# M2_Shield_Proto_V1_3.net
KiCad netlist of a schematic drawn in EAGLE
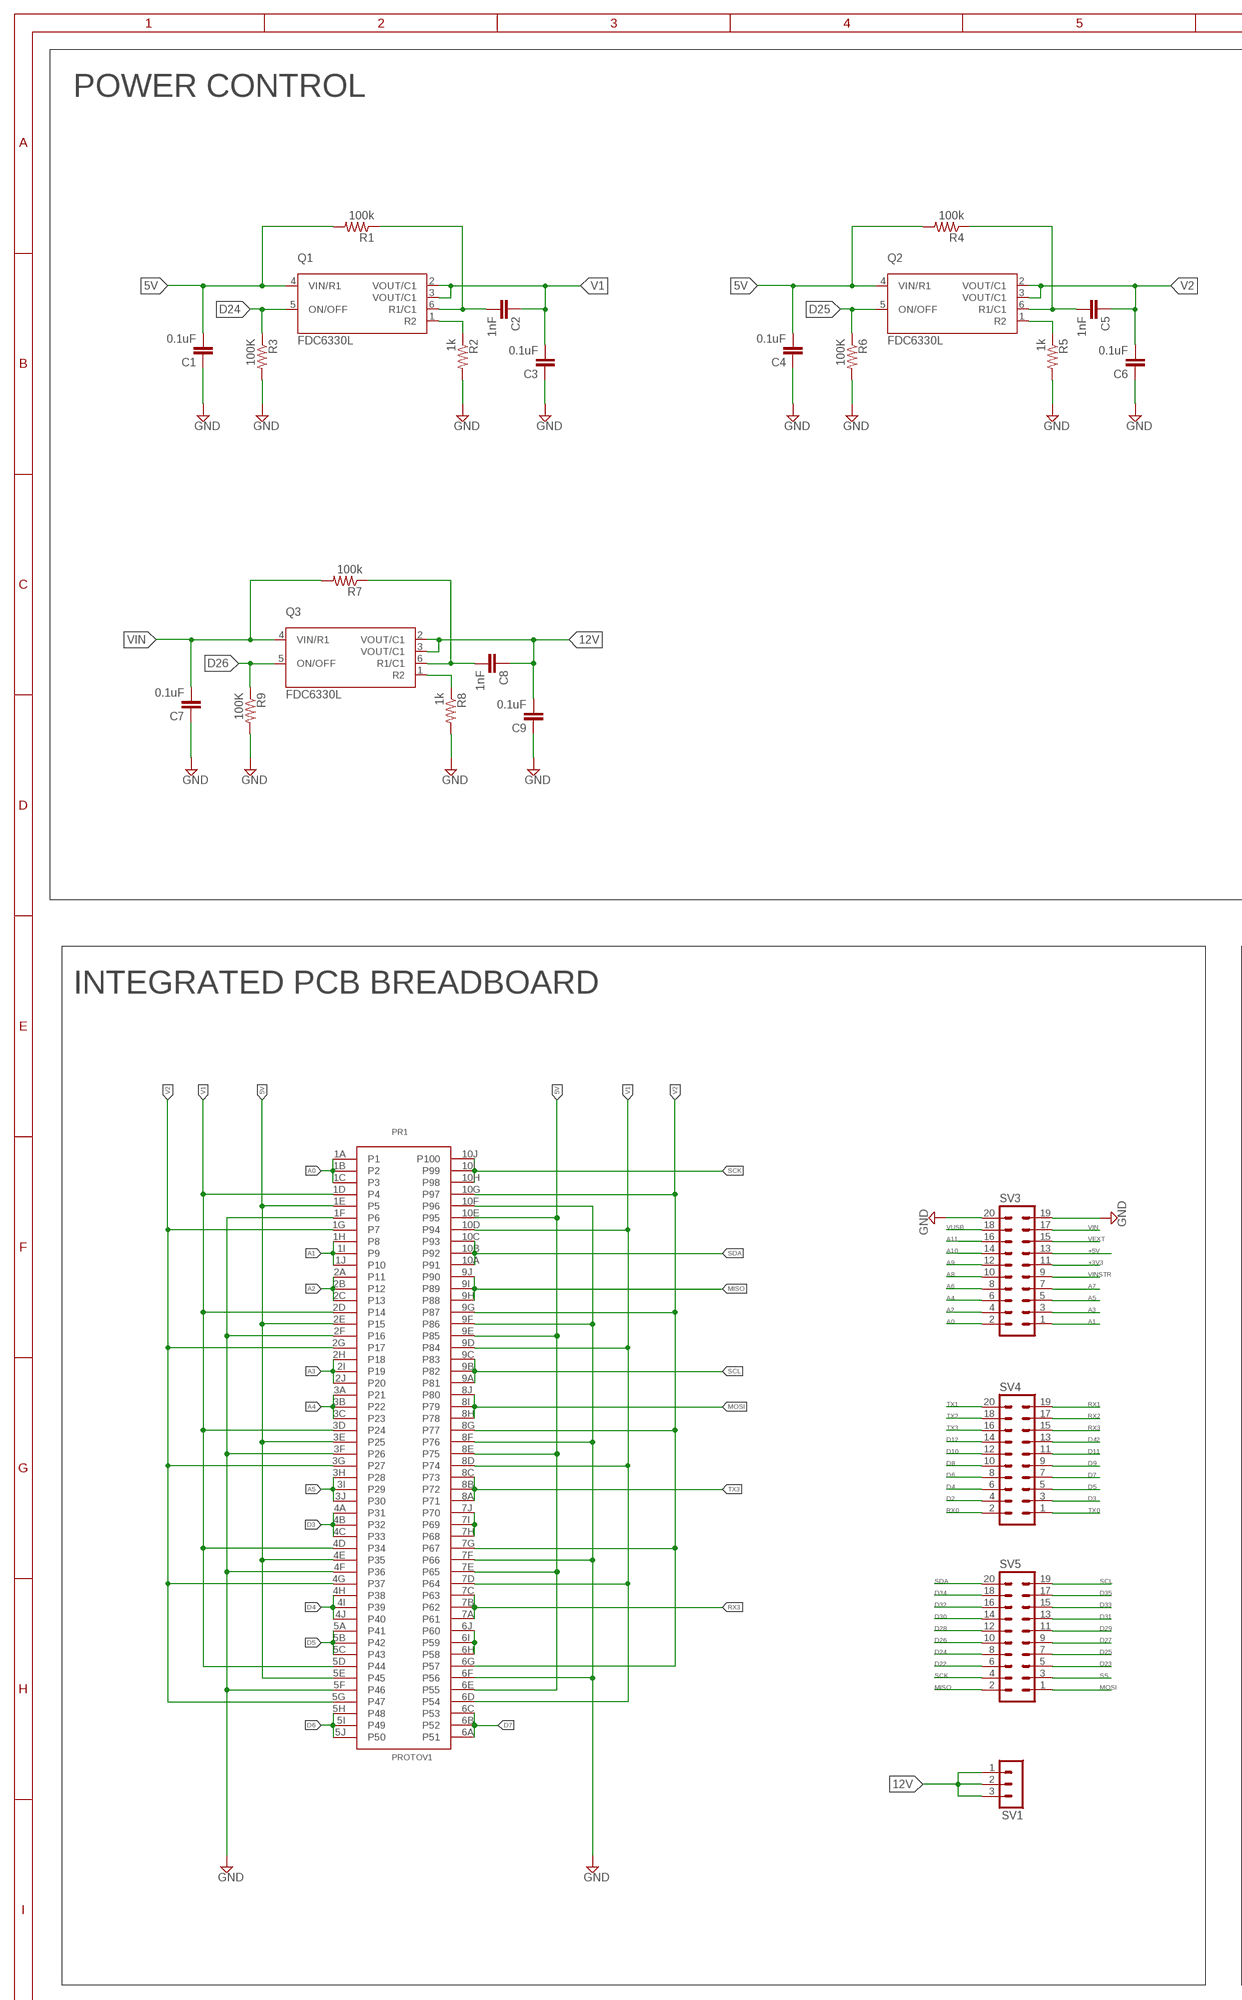
[diagram p0: schematic, sheet 1, part 1 of 2]
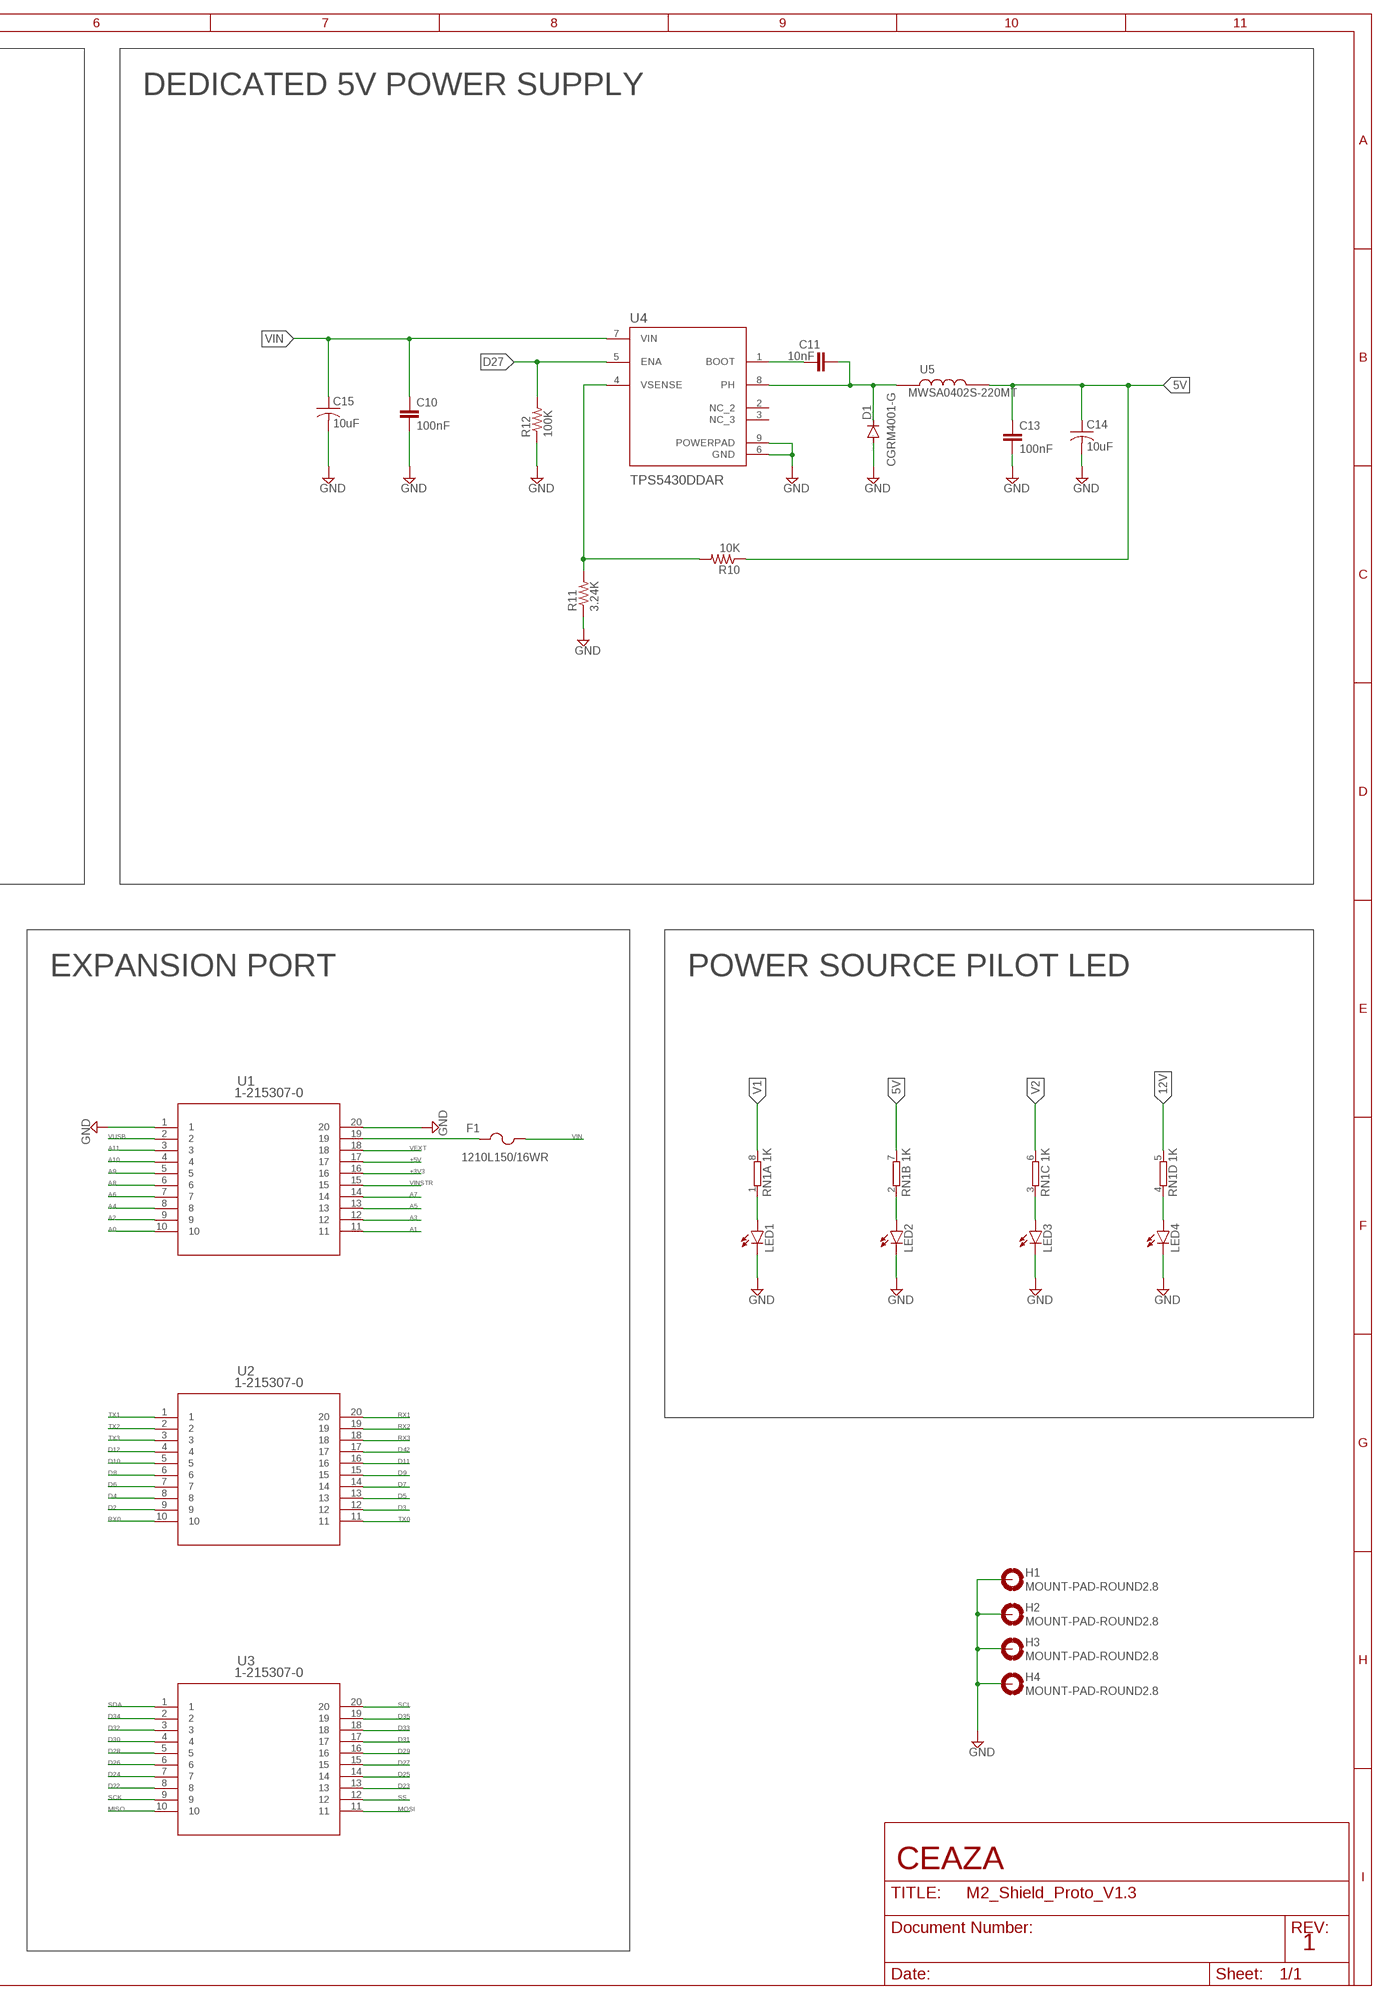
[diagram p1: schematic, sheet 1, part 2 of 2]

(export (version "E")
  (design (tool "Eeschema 10.0.6"))
  (components
    (comp (ref "C1")
      (value "0.1uF")
      (footprint "eagle-import:C0603")
      (libsource (lib "eagle-import") (part "C-EUC0603"))
    )
    (comp (ref "C2")
      (value "1nF")
      (footprint "eagle-import:C0603")
      (libsource (lib "eagle-import") (part "C-EUC0603"))
    )
    (comp (ref "C3")
      (value "0.1uF")
      (footprint "eagle-import:C0603")
      (libsource (lib "eagle-import") (part "C-EUC0603"))
    )
    (comp (ref "C4")
      (value "0.1uF")
      (footprint "eagle-import:C0603")
      (libsource (lib "eagle-import") (part "C-EUC0603"))
    )
    (comp (ref "C5")
      (value "1nF")
      (footprint "eagle-import:C0603")
      (libsource (lib "eagle-import") (part "C-EUC0603"))
    )
    (comp (ref "C6")
      (value "0.1uF")
      (footprint "eagle-import:C0603")
      (libsource (lib "eagle-import") (part "C-EUC0603"))
    )
    (comp (ref "C7")
      (value "0.1uF")
      (footprint "eagle-import:C0603")
      (libsource (lib "eagle-import") (part "C-EUC0603"))
    )
    (comp (ref "C8")
      (value "1nF")
      (footprint "eagle-import:C0603")
      (libsource (lib "eagle-import") (part "C-EUC0603"))
    )
    (comp (ref "C9")
      (value "0.1uF")
      (footprint "eagle-import:C0603")
      (libsource (lib "eagle-import") (part "C-EUC0603"))
    )
    (comp (ref "C10")
      (value "100nF")
      (footprint "eagle-import:C0603")
      (libsource (lib "eagle-import") (part "C-EUC0603"))
    )
    (comp (ref "C11")
      (value "10nF")
      (footprint "eagle-import:C0603")
      (libsource (lib "eagle-import") (part "C-EUC0603"))
    )
    (comp (ref "C13")
      (value "100nF")
      (footprint "eagle-import:C0603")
      (libsource (lib "eagle-import") (part "C-EUC0603"))
    )
    (comp (ref "C14")
      (value "10uF")
      (footprint "eagle-import:C0603")
      (libsource (lib "eagle-import") (part "C-USC0603"))
    )
    (comp (ref "C15")
      (value "10uF")
      (footprint "eagle-import:C0603")
      (libsource (lib "eagle-import") (part "C-USC0603"))
    )
    (comp (ref "D1")
      (value "CGRM4001-G")
      (footprint "eagle-import:SOD-123_MINI-SMA")
      (libsource (lib "eagle-import") (part "CGRM400-G1"))
    )
    (comp (ref "F1")
      (value "1210L150/16WR")
      (footprint "eagle-import:1210LSERIES")
      (libsource (lib "eagle-import") (part "1210L150/16WR"))
    )
    (comp (ref "H1")
      (value "MOUNT-PAD-ROUND2.8")
      (footprint "eagle-import:2,8-PAD")
      (libsource (lib "eagle-import") (part "MOUNT-PAD-ROUND2.8"))
    )
    (comp (ref "H2")
      (value "MOUNT-PAD-ROUND2.8")
      (footprint "eagle-import:2,8-PAD")
      (libsource (lib "eagle-import") (part "MOUNT-PAD-ROUND2.8"))
    )
    (comp (ref "H3")
      (value "MOUNT-PAD-ROUND2.8")
      (footprint "eagle-import:2,8-PAD")
      (libsource (lib "eagle-import") (part "MOUNT-PAD-ROUND2.8"))
    )
    (comp (ref "H4")
      (value "MOUNT-PAD-ROUND2.8")
      (footprint "eagle-import:2,8-PAD")
      (libsource (lib "eagle-import") (part "MOUNT-PAD-ROUND2.8"))
    )
    (comp (ref "LED1")
      (value "LEDCHIP-LED0805")
      (footprint "eagle-import:CHIP-LED0805")
      (libsource (lib "eagle-import") (part "LEDCHIP-LED0805"))
    )
    (comp (ref "LED2")
      (value "LEDCHIP-LED0805")
      (footprint "eagle-import:CHIP-LED0805")
      (libsource (lib "eagle-import") (part "LEDCHIP-LED0805"))
    )
    (comp (ref "LED3")
      (value "LEDCHIP-LED0805")
      (footprint "eagle-import:CHIP-LED0805")
      (libsource (lib "eagle-import") (part "LEDCHIP-LED0805"))
    )
    (comp (ref "LED4")
      (value "LEDCHIP-LED0805")
      (footprint "eagle-import:CHIP-LED0805")
      (libsource (lib "eagle-import") (part "LEDCHIP-LED0805"))
    )
    (comp (ref "PR1")
      (value "PROTOV1")
      (footprint "eagle-import:PROTOV1")
      (libsource (lib "eagle-import") (part "PROTOV1"))
    )
    (comp (ref "Q1")
      (value "FDC6330L")
      (footprint "eagle-import:SOT95P280X110-6N")
      (fields (field (name "DIGI-KEY_PART_NUMBER") "FDC6330LCT-ND") (field (name "MF") "ON Semiconductor"))
      (libsource (lib "eagle-import") (part "FDC6330L"))
    )
    (comp (ref "Q2")
      (value "FDC6330L")
      (footprint "eagle-import:SOT95P280X110-6N")
      (fields (field (name "DIGI-KEY_PART_NUMBER") "FDC6330LCT-ND") (field (name "MF") "ON Semiconductor"))
      (libsource (lib "eagle-import") (part "FDC6330L"))
    )
    (comp (ref "Q3")
      (value "FDC6330L")
      (footprint "eagle-import:SOT95P280X110-6N")
      (fields (field (name "DIGI-KEY_PART_NUMBER") "FDC6330LCT-ND") (field (name "MF") "ON Semiconductor"))
      (libsource (lib "eagle-import") (part "FDC6330L"))
    )
    (comp (ref "R1")
      (value "100k")
      (footprint "eagle-import:R0603")
      (libsource (lib "eagle-import") (part "R-US_R0603"))
    )
    (comp (ref "R2")
      (value "1k")
      (footprint "eagle-import:R0603")
      (libsource (lib "eagle-import") (part "R-US_R0603"))
    )
    (comp (ref "R3")
      (value "100K")
      (footprint "eagle-import:R0603")
      (libsource (lib "eagle-import") (part "R-US_R0603"))
    )
    (comp (ref "R4")
      (value "100k")
      (footprint "eagle-import:R0603")
      (libsource (lib "eagle-import") (part "R-US_R0603"))
    )
    (comp (ref "R5")
      (value "1k")
      (footprint "eagle-import:R0603")
      (libsource (lib "eagle-import") (part "R-US_R0603"))
    )
    (comp (ref "R6")
      (value "100K")
      (footprint "eagle-import:R0603")
      (libsource (lib "eagle-import") (part "R-US_R0603"))
    )
    (comp (ref "R7")
      (value "100k")
      (footprint "eagle-import:R0603")
      (libsource (lib "eagle-import") (part "R-US_R0603"))
    )
    (comp (ref "R8")
      (value "1k")
      (footprint "eagle-import:R0603")
      (libsource (lib "eagle-import") (part "R-US_R0603"))
    )
    (comp (ref "R9")
      (value "100K")
      (footprint "eagle-import:R0603")
      (libsource (lib "eagle-import") (part "R-US_R0603"))
    )
    (comp (ref "R10")
      (value "10K")
      (footprint "eagle-import:R0603")
      (libsource (lib "eagle-import") (part "R-US_R0603"))
    )
    (comp (ref "R11")
      (value "3.24K")
      (footprint "eagle-import:R0603")
      (libsource (lib "eagle-import") (part "R-US_R0603"))
    )
    (comp (ref "R12")
      (value "100K")
      (footprint "eagle-import:R0603")
      (libsource (lib "eagle-import") (part "R-US_R0603"))
    )
    (comp (ref "RN1")
      (value "1K")
      (footprint "eagle-import:0603-ARV")
      (libsource (lib "eagle-import") (part "4R-N0603-ARV"))
    )
    (comp (ref "SV1")
      (value "MA03-1")
      (footprint "eagle-import:MA03-1")
      (libsource (lib "eagle-import") (part "MA03-1"))
    )
    (comp (ref "SV3")
      (value "MA10-2")
      (footprint "eagle-import:MA10-2")
      (libsource (lib "eagle-import") (part "MA10-2"))
    )
    (comp (ref "SV4")
      (value "MA10-2")
      (footprint "eagle-import:MA10-2")
      (libsource (lib "eagle-import") (part "MA10-2"))
    )
    (comp (ref "SV5")
      (value "MA10-2")
      (footprint "eagle-import:MA10-2")
      (libsource (lib "eagle-import") (part "MA10-2"))
    )
    (comp (ref "U1")
      (value "1-215307-0")
      (footprint "eagle-import:1-215307-0")
      (libsource (lib "eagle-import") (part "1-215307-0"))
    )
    (comp (ref "U2")
      (value "1-215307-0")
      (footprint "eagle-import:1-215307-0")
      (libsource (lib "eagle-import") (part "1-215307-0"))
    )
    (comp (ref "U3")
      (value "1-215307-0")
      (footprint "eagle-import:1-215307-0")
      (libsource (lib "eagle-import") (part "1-215307-0"))
    )
    (comp (ref "U4")
      (value "TPS5430DDAR")
      (footprint "eagle-import:CONV_TPS5430DDAR")
      (fields (field (name "MF") "Texas Instruments"))
      (libsource (lib "eagle-import") (part "TPS5430DDAR"))
    )
    (comp (ref "U5")
      (value "MWSA0402S-220MT")
      (footprint "eagle-import:MWSA0402S-220MT")
      (libsource (lib "eagle-import") (part "MWSA0402S-220MT"))
    )
  )
  (nets
    (net (code "1") (name "/+3V3") (class "Default")
      (node (ref "SV3") (pin "11") (pinfunction "11_11") (pintype "passive"))
      (node (ref "U1") (pin "16") (pinfunction "16_16") (pintype "passive"))
    )
    (net (code "2") (name "/+5V") (class "Default")
      (node (ref "SV3") (pin "13") (pinfunction "13_13") (pintype "passive"))
      (node (ref "U1") (pin "17") (pinfunction "17_17") (pintype "passive"))
    )
    (net (code "3") (name "/A6") (class "Default")
      (node (ref "SV3") (pin "8") (pinfunction "8_8") (pintype "passive"))
      (node (ref "U1") (pin "7") (pinfunction "7_7") (pintype "passive"))
    )
    (net (code "4") (name "/A7") (class "Default")
      (node (ref "SV3") (pin "7") (pinfunction "7_7") (pintype "passive"))
      (node (ref "U1") (pin "14") (pinfunction "14_14") (pintype "passive"))
    )
    (net (code "5") (name "/A8") (class "Default")
      (node (ref "SV3") (pin "10") (pinfunction "10_10") (pintype "passive"))
      (node (ref "U1") (pin "6") (pinfunction "6_6") (pintype "passive"))
    )
    (net (code "6") (name "/A9") (class "Default")
      (node (ref "SV3") (pin "12") (pinfunction "12_12") (pintype "passive"))
      (node (ref "U1") (pin "5") (pinfunction "5_5") (pintype "passive"))
    )
    (net (code "7") (name "/A10") (class "Default")
      (node (ref "SV3") (pin "14") (pinfunction "14_14") (pintype "passive"))
      (node (ref "U1") (pin "4") (pinfunction "4_4") (pintype "passive"))
    )
    (net (code "8") (name "/A11") (class "Default")
      (node (ref "SV3") (pin "16") (pinfunction "16_16") (pintype "passive"))
      (node (ref "U1") (pin "3") (pinfunction "3_3") (pintype "passive"))
    )
    (net (code "9") (name "/D2") (class "Default")
      (node (ref "SV4") (pin "4") (pinfunction "4_4") (pintype "passive"))
      (node (ref "U2") (pin "9") (pinfunction "9_9") (pintype "passive"))
    )
    (net (code "10") (name "/D8") (class "Default")
      (node (ref "SV4") (pin "10") (pinfunction "10_10") (pintype "passive"))
      (node (ref "U2") (pin "6") (pinfunction "6_6") (pintype "passive"))
    )
    (net (code "11") (name "/D9") (class "Default")
      (node (ref "SV4") (pin "9") (pinfunction "9_9") (pintype "passive"))
      (node (ref "U2") (pin "15") (pinfunction "15_15") (pintype "passive"))
    )
    (net (code "12") (name "/D10") (class "Default")
      (node (ref "SV4") (pin "12") (pinfunction "12_12") (pintype "passive"))
      (node (ref "U2") (pin "5") (pinfunction "5_5") (pintype "passive"))
    )
    (net (code "13") (name "/D11") (class "Default")
      (node (ref "SV4") (pin "11") (pinfunction "11_11") (pintype "passive"))
      (node (ref "U2") (pin "16") (pinfunction "16_16") (pintype "passive"))
    )
    (net (code "14") (name "/D12") (class "Default")
      (node (ref "SV4") (pin "14") (pinfunction "14_14") (pintype "passive"))
      (node (ref "U2") (pin "4") (pinfunction "4_4") (pintype "passive"))
    )
    (net (code "15") (name "/D22") (class "Default")
      (node (ref "SV5") (pin "6") (pinfunction "6_6") (pintype "passive"))
      (node (ref "U3") (pin "8") (pinfunction "8_8") (pintype "passive"))
    )
    (net (code "16") (name "/D23") (class "Default")
      (node (ref "SV5") (pin "5") (pinfunction "5_5") (pintype "passive"))
      (node (ref "U3") (pin "13") (pinfunction "13_13") (pintype "passive"))
    )
    (net (code "17") (name "/D28") (class "Default")
      (node (ref "SV5") (pin "12") (pinfunction "12_12") (pintype "passive"))
      (node (ref "U3") (pin "5") (pinfunction "5_5") (pintype "passive"))
    )
    (net (code "18") (name "/D29") (class "Default")
      (node (ref "SV5") (pin "11") (pinfunction "11_11") (pintype "passive"))
      (node (ref "U3") (pin "16") (pinfunction "16_16") (pintype "passive"))
    )
    (net (code "19") (name "/D30") (class "Default")
      (node (ref "SV5") (pin "14") (pinfunction "14_14") (pintype "passive"))
      (node (ref "U3") (pin "4") (pinfunction "4_4") (pintype "passive"))
    )
    (net (code "20") (name "/D31") (class "Default")
      (node (ref "SV5") (pin "13") (pinfunction "13_13") (pintype "passive"))
      (node (ref "U3") (pin "17") (pinfunction "17_17") (pintype "passive"))
    )
    (net (code "21") (name "/D32") (class "Default")
      (node (ref "SV5") (pin "16") (pinfunction "16_16") (pintype "passive"))
      (node (ref "U3") (pin "3") (pinfunction "3_3") (pintype "passive"))
    )
    (net (code "22") (name "/D33") (class "Default")
      (node (ref "SV5") (pin "15") (pinfunction "15_15") (pintype "passive"))
      (node (ref "U3") (pin "18") (pinfunction "18_18") (pintype "passive"))
    )
    (net (code "23") (name "/D34") (class "Default")
      (node (ref "SV5") (pin "18") (pinfunction "18_18") (pintype "passive"))
      (node (ref "U3") (pin "2") (pinfunction "2_2") (pintype "passive"))
    )
    (net (code "24") (name "/D35") (class "Default")
      (node (ref "SV5") (pin "17") (pinfunction "17_17") (pintype "passive"))
      (node (ref "U3") (pin "19") (pinfunction "19_19") (pintype "passive"))
    )
    (net (code "25") (name "/D42") (class "Default")
      (node (ref "SV4") (pin "13") (pinfunction "13_13") (pintype "passive"))
      (node (ref "U2") (pin "17") (pinfunction "17_17") (pintype "passive"))
    )
    (net (code "26") (name "/RX0") (class "Default")
      (node (ref "SV4") (pin "2") (pinfunction "2_2") (pintype "passive"))
      (node (ref "U2") (pin "10") (pinfunction "10_10") (pintype "passive"))
    )
    (net (code "27") (name "/RX1") (class "Default")
      (node (ref "SV4") (pin "19") (pinfunction "19_19") (pintype "passive"))
      (node (ref "U2") (pin "20") (pinfunction "20_20") (pintype "passive"))
    )
    (net (code "28") (name "/RX2") (class "Default")
      (node (ref "SV4") (pin "17") (pinfunction "17_17") (pintype "passive"))
      (node (ref "U2") (pin "19") (pinfunction "19_19") (pintype "passive"))
    )
    (net (code "29") (name "/SS") (class "Default")
      (node (ref "SV5") (pin "3") (pinfunction "3_3") (pintype "passive"))
      (node (ref "U3") (pin "12") (pinfunction "12_12") (pintype "passive"))
    )
    (net (code "30") (name "/TX0") (class "Default")
      (node (ref "SV4") (pin "1") (pinfunction "1_1") (pintype "passive"))
      (node (ref "U2") (pin "11") (pinfunction "11_11") (pintype "passive"))
    )
    (net (code "31") (name "/TX1") (class "Default")
      (node (ref "SV4") (pin "20") (pinfunction "20_20") (pintype "passive"))
      (node (ref "U2") (pin "1") (pinfunction "1_1") (pintype "passive"))
    )
    (net (code "32") (name "/TX2") (class "Default")
      (node (ref "SV4") (pin "18") (pinfunction "18_18") (pintype "passive"))
      (node (ref "U2") (pin "2") (pinfunction "2_2") (pintype "passive"))
    )
    (net (code "33") (name "/VEXT") (class "Default")
      (node (ref "SV3") (pin "15") (pinfunction "15_15") (pintype "passive"))
      (node (ref "U1") (pin "18") (pinfunction "18_18") (pintype "passive"))
    )
    (net (code "34") (name "/VINSTR") (class "Default")
      (node (ref "SV3") (pin "9") (pinfunction "9_9") (pintype "passive"))
      (node (ref "U1") (pin "15") (pinfunction "15_15") (pintype "passive"))
    )
    (net (code "35") (name "/VUSB") (class "Default")
      (node (ref "SV3") (pin "18") (pinfunction "18_18") (pintype "passive"))
      (node (ref "U1") (pin "2") (pinfunction "2_2") (pintype "passive"))
    )
    (net (code "36") (name "5V") (class "Default")
      (node (ref "C1") (pin "2") (pinfunction "2_2") (pintype "passive"))
      (node (ref "C13") (pin "1") (pinfunction "1_1") (pintype "passive"))
      (node (ref "C14") (pin "1") (pinfunction "1_1") (pintype "passive"))
      (node (ref "C4") (pin "2") (pinfunction "2_2") (pintype "passive"))
      (node (ref "PR1") (pin "10E") (pinfunction "P95_10E") (pintype "bidirectional"))
      (node (ref "PR1") (pin "1E") (pinfunction "P5_1E") (pintype "bidirectional"))
      (node (ref "PR1") (pin "2E") (pinfunction "P15_2E") (pintype "bidirectional"))
      (node (ref "PR1") (pin "3E") (pinfunction "P25_3E") (pintype "bidirectional"))
      (node (ref "PR1") (pin "4E") (pinfunction "P35_4E") (pintype "bidirectional"))
      (node (ref "PR1") (pin "5E") (pinfunction "P45_5E") (pintype "bidirectional"))
      (node (ref "PR1") (pin "6E") (pinfunction "P55_6E") (pintype "bidirectional"))
      (node (ref "PR1") (pin "7E") (pinfunction "P65_7E") (pintype "bidirectional"))
      (node (ref "PR1") (pin "8E") (pinfunction "P75_8E") (pintype "bidirectional"))
      (node (ref "PR1") (pin "9E") (pinfunction "P85_9E") (pintype "bidirectional"))
      (node (ref "Q1") (pin "4") (pinfunction "VIN/R1_4") (pintype "input"))
      (node (ref "Q2") (pin "4") (pinfunction "VIN/R1_4") (pintype "input"))
      (node (ref "R1") (pin "2") (pinfunction "2_2") (pintype "passive"))
      (node (ref "R10") (pin "1") (pinfunction "1_1") (pintype "passive"))
      (node (ref "R4") (pin "2") (pinfunction "2_2") (pintype "passive"))
      (node (ref "RN1") (pin "7") (pinfunction "2_7") (pintype "passive"))
      (node (ref "U5") (pin "P$2") (pinfunction "P$2_P$2") (pintype "bidirectional"))
    )
    (net (code "37") (name "12V") (class "Default")
      (node (ref "C8") (pin "1") (pinfunction "1_1") (pintype "passive"))
      (node (ref "C9") (pin "2") (pinfunction "2_2") (pintype "passive"))
      (node (ref "Q3") (pin "2") (pinfunction "VOUT/C1_2") (pintype "output"))
      (node (ref "Q3") (pin "3") (pinfunction "VOUT/C1_3") (pintype "output"))
      (node (ref "RN1") (pin "5") (pinfunction "2_5") (pintype "passive"))
      (node (ref "SV1") (pin "1") (pinfunction "1_1") (pintype "passive"))
      (node (ref "SV1") (pin "2") (pinfunction "2_2") (pintype "passive"))
      (node (ref "SV1") (pin "3") (pinfunction "3_3") (pintype "passive"))
    )
    (net (code "38") (name "A0") (class "Default")
      (node (ref "PR1") (pin "1A") (pinfunction "P1_1A") (pintype "bidirectional"))
      (node (ref "PR1") (pin "1B") (pinfunction "P2_1B") (pintype "bidirectional"))
      (node (ref "PR1") (pin "1C") (pinfunction "P3_1C") (pintype "bidirectional"))
      (node (ref "SV3") (pin "2") (pinfunction "2_2") (pintype "passive"))
      (node (ref "U1") (pin "10") (pinfunction "10_10") (pintype "passive"))
    )
    (net (code "39") (name "A1") (class "Default")
      (node (ref "PR1") (pin "1H") (pinfunction "P8_1H") (pintype "bidirectional"))
      (node (ref "PR1") (pin "1I") (pinfunction "P9_1I") (pintype "bidirectional"))
      (node (ref "PR1") (pin "1J") (pinfunction "P10_1J") (pintype "bidirectional"))
      (node (ref "SV3") (pin "1") (pinfunction "1_1") (pintype "passive"))
      (node (ref "U1") (pin "11") (pinfunction "11_11") (pintype "passive"))
    )
    (net (code "40") (name "A2") (class "Default")
      (node (ref "PR1") (pin "2A") (pinfunction "P11_2A") (pintype "bidirectional"))
      (node (ref "PR1") (pin "2B") (pinfunction "P12_2B") (pintype "bidirectional"))
      (node (ref "PR1") (pin "2C") (pinfunction "P13_2C") (pintype "bidirectional"))
      (node (ref "SV3") (pin "4") (pinfunction "4_4") (pintype "passive"))
      (node (ref "U1") (pin "9") (pinfunction "9_9") (pintype "passive"))
    )
    (net (code "41") (name "A3") (class "Default")
      (node (ref "PR1") (pin "2H") (pinfunction "P18_2H") (pintype "bidirectional"))
      (node (ref "PR1") (pin "2I") (pinfunction "P19_2I") (pintype "bidirectional"))
      (node (ref "PR1") (pin "2J") (pinfunction "P20_2J") (pintype "bidirectional"))
      (node (ref "SV3") (pin "3") (pinfunction "3_3") (pintype "passive"))
      (node (ref "U1") (pin "12") (pinfunction "12_12") (pintype "passive"))
    )
    (net (code "42") (name "A4") (class "Default")
      (node (ref "PR1") (pin "3A") (pinfunction "P21_3A") (pintype "bidirectional"))
      (node (ref "PR1") (pin "3B") (pinfunction "P22_3B") (pintype "bidirectional"))
      (node (ref "PR1") (pin "3C") (pinfunction "P23_3C") (pintype "bidirectional"))
      (node (ref "SV3") (pin "6") (pinfunction "6_6") (pintype "passive"))
      (node (ref "U1") (pin "8") (pinfunction "8_8") (pintype "passive"))
    )
    (net (code "43") (name "A5") (class "Default")
      (node (ref "PR1") (pin "3H") (pinfunction "P28_3H") (pintype "bidirectional"))
      (node (ref "PR1") (pin "3I") (pinfunction "P29_3I") (pintype "bidirectional"))
      (node (ref "PR1") (pin "3J") (pinfunction "P30_3J") (pintype "bidirectional"))
      (node (ref "SV3") (pin "5") (pinfunction "5_5") (pintype "passive"))
      (node (ref "U1") (pin "13") (pinfunction "13_13") (pintype "passive"))
    )
    (net (code "44") (name "D3") (class "Default")
      (node (ref "PR1") (pin "4A") (pinfunction "P31_4A") (pintype "bidirectional"))
      (node (ref "PR1") (pin "4B") (pinfunction "P32_4B") (pintype "bidirectional"))
      (node (ref "PR1") (pin "4C") (pinfunction "P33_4C") (pintype "bidirectional"))
      (node (ref "SV4") (pin "3") (pinfunction "3_3") (pintype "passive"))
      (node (ref "U2") (pin "12") (pinfunction "12_12") (pintype "passive"))
    )
    (net (code "45") (name "D4") (class "Default")
      (node (ref "PR1") (pin "4H") (pinfunction "P38_4H") (pintype "bidirectional"))
      (node (ref "PR1") (pin "4I") (pinfunction "P39_4I") (pintype "bidirectional"))
      (node (ref "PR1") (pin "4J") (pinfunction "P40_4J") (pintype "bidirectional"))
      (node (ref "SV4") (pin "6") (pinfunction "6_6") (pintype "passive"))
      (node (ref "U2") (pin "8") (pinfunction "8_8") (pintype "passive"))
    )
    (net (code "46") (name "D5") (class "Default")
      (node (ref "PR1") (pin "5A") (pinfunction "P41_5A") (pintype "bidirectional"))
      (node (ref "PR1") (pin "5B") (pinfunction "P42_5B") (pintype "bidirectional"))
      (node (ref "PR1") (pin "5C") (pinfunction "P43_5C") (pintype "bidirectional"))
      (node (ref "SV4") (pin "5") (pinfunction "5_5") (pintype "passive"))
      (node (ref "U2") (pin "13") (pinfunction "13_13") (pintype "passive"))
    )
    (net (code "47") (name "D6") (class "Default")
      (node (ref "PR1") (pin "5H") (pinfunction "P48_5H") (pintype "bidirectional"))
      (node (ref "PR1") (pin "5I") (pinfunction "P49_5I") (pintype "bidirectional"))
      (node (ref "PR1") (pin "5J") (pinfunction "P50_5J") (pintype "bidirectional"))
      (node (ref "SV4") (pin "8") (pinfunction "8_8") (pintype "passive"))
      (node (ref "U2") (pin "7") (pinfunction "7_7") (pintype "passive"))
    )
    (net (code "48") (name "D7") (class "Default")
      (node (ref "PR1") (pin "6A") (pinfunction "P51_6A") (pintype "bidirectional"))
      (node (ref "PR1") (pin "6B") (pinfunction "P52_6B") (pintype "bidirectional"))
      (node (ref "PR1") (pin "6C") (pinfunction "P53_6C") (pintype "bidirectional"))
      (node (ref "SV4") (pin "7") (pinfunction "7_7") (pintype "passive"))
      (node (ref "U2") (pin "14") (pinfunction "14_14") (pintype "passive"))
    )
    (net (code "49") (name "D24") (class "Default")
      (node (ref "Q1") (pin "5") (pinfunction "ON/OFF_5") (pintype "input"))
      (node (ref "R3") (pin "1") (pinfunction "1_1") (pintype "passive"))
      (node (ref "SV5") (pin "8") (pinfunction "8_8") (pintype "passive"))
      (node (ref "U3") (pin "7") (pinfunction "7_7") (pintype "passive"))
    )
    (net (code "50") (name "D25") (class "Default")
      (node (ref "Q2") (pin "5") (pinfunction "ON/OFF_5") (pintype "input"))
      (node (ref "R6") (pin "1") (pinfunction "1_1") (pintype "passive"))
      (node (ref "SV5") (pin "7") (pinfunction "7_7") (pintype "passive"))
      (node (ref "U3") (pin "14") (pinfunction "14_14") (pintype "passive"))
    )
    (net (code "51") (name "D26") (class "Default")
      (node (ref "Q3") (pin "5") (pinfunction "ON/OFF_5") (pintype "input"))
      (node (ref "R9") (pin "1") (pinfunction "1_1") (pintype "passive"))
      (node (ref "SV5") (pin "10") (pinfunction "10_10") (pintype "passive"))
      (node (ref "U3") (pin "6") (pinfunction "6_6") (pintype "passive"))
    )
    (net (code "52") (name "D27") (class "Default")
      (node (ref "R12") (pin "2") (pinfunction "2_2") (pintype "passive"))
      (node (ref "SV5") (pin "9") (pinfunction "9_9") (pintype "passive"))
      (node (ref "U3") (pin "15") (pinfunction "15_15") (pintype "passive"))
      (node (ref "U4") (pin "5") (pinfunction "ENA_5") (pintype "input"))
    )
    (net (code "53") (name "GND") (class "Default")
      (node (ref "C1") (pin "1") (pinfunction "1_1") (pintype "passive"))
      (node (ref "C10") (pin "2") (pinfunction "2_2") (pintype "passive"))
      (node (ref "C13") (pin "2") (pinfunction "2_2") (pintype "passive"))
      (node (ref "C14") (pin "2") (pinfunction "2_2") (pintype "passive"))
      (node (ref "C15") (pin "2") (pinfunction "2_2") (pintype "passive"))
      (node (ref "C3") (pin "1") (pinfunction "1_1") (pintype "passive"))
      (node (ref "C4") (pin "1") (pinfunction "1_1") (pintype "passive"))
      (node (ref "C6") (pin "1") (pinfunction "1_1") (pintype "passive"))
      (node (ref "C7") (pin "1") (pinfunction "1_1") (pintype "passive"))
      (node (ref "C9") (pin "1") (pinfunction "1_1") (pintype "passive"))
      (node (ref "D1") (pin "A") (pinfunction "A_A") (pintype "passive"))
      (node (ref "H1") (pin "B2,8") (pinfunction "MOUNT_B2,8") (pintype "passive"))
      (node (ref "H2") (pin "B2,8") (pinfunction "MOUNT_B2,8") (pintype "passive"))
      (node (ref "H3") (pin "B2,8") (pinfunction "MOUNT_B2,8") (pintype "passive"))
      (node (ref "H4") (pin "B2,8") (pinfunction "MOUNT_B2,8") (pintype "passive"))
      (node (ref "LED1") (pin "C") (pinfunction "C_C") (pintype "passive"))
      (node (ref "LED2") (pin "C") (pinfunction "C_C") (pintype "passive"))
      (node (ref "LED3") (pin "C") (pinfunction "C_C") (pintype "passive"))
      (node (ref "LED4") (pin "C") (pinfunction "C_C") (pintype "passive"))
      (node (ref "PR1") (pin "10F") (pinfunction "P96_10F") (pintype "bidirectional"))
      (node (ref "PR1") (pin "1F") (pinfunction "P6_1F") (pintype "bidirectional"))
      (node (ref "PR1") (pin "2F") (pinfunction "P16_2F") (pintype "bidirectional"))
      (node (ref "PR1") (pin "3F") (pinfunction "P26_3F") (pintype "bidirectional"))
      (node (ref "PR1") (pin "4F") (pinfunction "P36_4F") (pintype "bidirectional"))
      (node (ref "PR1") (pin "5F") (pinfunction "P46_5F") (pintype "bidirectional"))
      (node (ref "PR1") (pin "6F") (pinfunction "P56_6F") (pintype "bidirectional"))
      (node (ref "PR1") (pin "7F") (pinfunction "P66_7F") (pintype "bidirectional"))
      (node (ref "PR1") (pin "8F") (pinfunction "P76_8F") (pintype "bidirectional"))
      (node (ref "PR1") (pin "9F") (pinfunction "P86_9F") (pintype "bidirectional"))
      (node (ref "R11") (pin "1") (pinfunction "1_1") (pintype "passive"))
      (node (ref "R12") (pin "1") (pinfunction "1_1") (pintype "passive"))
      (node (ref "R2") (pin "2") (pinfunction "2_2") (pintype "passive"))
      (node (ref "R3") (pin "2") (pinfunction "2_2") (pintype "passive"))
      (node (ref "R5") (pin "2") (pinfunction "2_2") (pintype "passive"))
      (node (ref "R6") (pin "2") (pinfunction "2_2") (pintype "passive"))
      (node (ref "R8") (pin "2") (pinfunction "2_2") (pintype "passive"))
      (node (ref "R9") (pin "2") (pinfunction "2_2") (pintype "passive"))
      (node (ref "SV3") (pin "19") (pinfunction "19_19") (pintype "passive"))
      (node (ref "SV3") (pin "20") (pinfunction "20_20") (pintype "passive"))
      (node (ref "U1") (pin "1") (pinfunction "1_1") (pintype "passive"))
      (node (ref "U1") (pin "20") (pinfunction "20_20") (pintype "passive"))
      (node (ref "U4") (pin "6") (pinfunction "GND_6") (pintype "power_in"))
      (node (ref "U4") (pin "9") (pinfunction "POWERPAD_9") (pintype "power_in"))
    )
    (net (code "54") (name "MISO") (class "Default")
      (node (ref "PR1") (pin "9H") (pinfunction "P88_9H") (pintype "bidirectional"))
      (node (ref "PR1") (pin "9I") (pinfunction "P89_9I") (pintype "bidirectional"))
      (node (ref "PR1") (pin "9J") (pinfunction "P90_9J") (pintype "bidirectional"))
      (node (ref "SV5") (pin "2") (pinfunction "2_2") (pintype "passive"))
      (node (ref "U3") (pin "10") (pinfunction "10_10") (pintype "passive"))
    )
    (net (code "55") (name "MOSI") (class "Default")
      (node (ref "PR1") (pin "8H") (pinfunction "P78_8H") (pintype "bidirectional"))
      (node (ref "PR1") (pin "8I") (pinfunction "P79_8I") (pintype "bidirectional"))
      (node (ref "PR1") (pin "8J") (pinfunction "P80_8J") (pintype "bidirectional"))
      (node (ref "SV5") (pin "1") (pinfunction "1_1") (pintype "passive"))
      (node (ref "U3") (pin "11") (pinfunction "11_11") (pintype "passive"))
    )
    (net (code "56") (name "Net-(F1-Pad1)") (class "Default")
      (node (ref "F1") (pin "1") (pinfunction "1_1") (pintype "passive"))
      (node (ref "U1") (pin "19") (pinfunction "19_19") (pintype "passive"))
    )
    (net (code "57") (name "Net-(LED1-PadA)") (class "Default")
      (node (ref "LED1") (pin "A") (pinfunction "A_A") (pintype "passive"))
      (node (ref "RN1") (pin "1") (pinfunction "1_1") (pintype "passive"))
    )
    (net (code "58") (name "Net-(PR1-P58)") (class "Default")
      (node (ref "PR1") (pin "6H") (pinfunction "P58_6H") (pintype "bidirectional"))
      (node (ref "PR1") (pin "6I") (pinfunction "P59_6I") (pintype "bidirectional"))
      (node (ref "PR1") (pin "6J") (pinfunction "P60_6J") (pintype "bidirectional"))
    )
    (net (code "59") (name "Net-(PR1-P68)") (class "Default")
      (node (ref "PR1") (pin "7H") (pinfunction "P68_7H") (pintype "bidirectional"))
      (node (ref "PR1") (pin "7I") (pinfunction "P69_7I") (pintype "bidirectional"))
      (node (ref "PR1") (pin "7J") (pinfunction "P70_7J") (pintype "bidirectional"))
    )
    (net (code "60") (name "Net-(Q1-R1{slash}C1)") (class "Default")
      (node (ref "C2") (pin "2") (pinfunction "2_2") (pintype "passive"))
      (node (ref "Q1") (pin "6") (pinfunction "R1/C1_6") (pintype "passive"))
      (node (ref "R1") (pin "1") (pinfunction "1_1") (pintype "passive"))
    )
    (net (code "61") (name "Net-(Q1-R2)") (class "Default")
      (node (ref "Q1") (pin "1") (pinfunction "R2_1") (pintype "passive"))
      (node (ref "R2") (pin "1") (pinfunction "1_1") (pintype "passive"))
    )
    (net (code "62") (name "Net-(Q2-R1{slash}C1)") (class "Default")
      (node (ref "C5") (pin "2") (pinfunction "2_2") (pintype "passive"))
      (node (ref "Q2") (pin "6") (pinfunction "R1/C1_6") (pintype "passive"))
      (node (ref "R4") (pin "1") (pinfunction "1_1") (pintype "passive"))
    )
    (net (code "63") (name "Net-(Q2-R2)") (class "Default")
      (node (ref "Q2") (pin "1") (pinfunction "R2_1") (pintype "passive"))
      (node (ref "R5") (pin "1") (pinfunction "1_1") (pintype "passive"))
    )
    (net (code "64") (name "Net-(Q3-R1{slash}C1)") (class "Default")
      (node (ref "C8") (pin "2") (pinfunction "2_2") (pintype "passive"))
      (node (ref "Q3") (pin "6") (pinfunction "R1/C1_6") (pintype "passive"))
      (node (ref "R7") (pin "1") (pinfunction "1_1") (pintype "passive"))
    )
    (net (code "65") (name "Net-(Q3-R2)") (class "Default")
      (node (ref "Q3") (pin "1") (pinfunction "R2_1") (pintype "passive"))
      (node (ref "R8") (pin "1") (pinfunction "1_1") (pintype "passive"))
    )
    (net (code "66") (name "Net-(RN1B-1)") (class "Default")
      (node (ref "LED2") (pin "A") (pinfunction "A_A") (pintype "passive"))
      (node (ref "RN1") (pin "2") (pinfunction "1_2") (pintype "passive"))
    )
    (net (code "67") (name "Net-(RN1C-1)") (class "Default")
      (node (ref "LED3") (pin "A") (pinfunction "A_A") (pintype "passive"))
      (node (ref "RN1") (pin "3") (pinfunction "1_3") (pintype "passive"))
    )
    (net (code "68") (name "Net-(RN1D-1)") (class "Default")
      (node (ref "LED4") (pin "A") (pinfunction "A_A") (pintype "passive"))
      (node (ref "RN1") (pin "4") (pinfunction "1_4") (pintype "passive"))
    )
    (net (code "69") (name "Net-(U4-BOOT)") (class "Default")
      (node (ref "C11") (pin "1") (pinfunction "1_1") (pintype "passive"))
      (node (ref "U4") (pin "1") (pinfunction "BOOT_1") (pintype "output"))
    )
    (net (code "70") (name "Net-(U4-PH)") (class "Default")
      (node (ref "C11") (pin "2") (pinfunction "2_2") (pintype "passive"))
      (node (ref "D1") (pin "C") (pinfunction "C_C") (pintype "passive"))
      (node (ref "U4") (pin "8") (pinfunction "PH_8") (pintype "bidirectional"))
      (node (ref "U5") (pin "P$1") (pinfunction "P$1_P$1") (pintype "bidirectional"))
    )
    (net (code "71") (name "Net-(U4-VSENSE)") (class "Default")
      (node (ref "R10") (pin "2") (pinfunction "2_2") (pintype "passive"))
      (node (ref "R11") (pin "2") (pinfunction "2_2") (pintype "passive"))
      (node (ref "U4") (pin "4") (pinfunction "VSENSE_4") (pintype "input"))
    )
    (net (code "72") (name "RX3") (class "Default")
      (node (ref "PR1") (pin "7A") (pinfunction "P61_7A") (pintype "bidirectional"))
      (node (ref "PR1") (pin "7B") (pinfunction "P62_7B") (pintype "bidirectional"))
      (node (ref "PR1") (pin "7C") (pinfunction "P63_7C") (pintype "bidirectional"))
      (node (ref "SV4") (pin "15") (pinfunction "15_15") (pintype "passive"))
      (node (ref "U2") (pin "18") (pinfunction "18_18") (pintype "passive"))
    )
    (net (code "73") (name "SCK") (class "Default")
      (node (ref "PR1") (pin "10H") (pinfunction "P98_10H") (pintype "bidirectional"))
      (node (ref "PR1") (pin "10I") (pinfunction "P99_10I") (pintype "bidirectional"))
      (node (ref "PR1") (pin "10J") (pinfunction "P100_10J") (pintype "bidirectional"))
      (node (ref "SV5") (pin "4") (pinfunction "4_4") (pintype "passive"))
      (node (ref "U3") (pin "9") (pinfunction "9_9") (pintype "passive"))
    )
    (net (code "74") (name "SCL") (class "Default")
      (node (ref "PR1") (pin "9A") (pinfunction "P81_9A") (pintype "bidirectional"))
      (node (ref "PR1") (pin "9B") (pinfunction "P82_9B") (pintype "bidirectional"))
      (node (ref "PR1") (pin "9C") (pinfunction "P83_9C") (pintype "bidirectional"))
      (node (ref "SV5") (pin "19") (pinfunction "19_19") (pintype "passive"))
      (node (ref "U3") (pin "20") (pinfunction "20_20") (pintype "passive"))
    )
    (net (code "75") (name "SDA") (class "Default")
      (node (ref "PR1") (pin "10A") (pinfunction "P91_10A") (pintype "bidirectional"))
      (node (ref "PR1") (pin "10B") (pinfunction "P92_10B") (pintype "bidirectional"))
      (node (ref "PR1") (pin "10C") (pinfunction "P93_10C") (pintype "bidirectional"))
      (node (ref "SV5") (pin "20") (pinfunction "20_20") (pintype "passive"))
      (node (ref "U3") (pin "1") (pinfunction "1_1") (pintype "passive"))
    )
    (net (code "76") (name "TX3") (class "Default")
      (node (ref "PR1") (pin "8A") (pinfunction "P71_8A") (pintype "bidirectional"))
      (node (ref "PR1") (pin "8B") (pinfunction "P72_8B") (pintype "bidirectional"))
      (node (ref "PR1") (pin "8C") (pinfunction "P73_8C") (pintype "bidirectional"))
      (node (ref "SV4") (pin "16") (pinfunction "16_16") (pintype "passive"))
      (node (ref "U2") (pin "3") (pinfunction "3_3") (pintype "passive"))
    )
    (net (code "77") (name "V1") (class "Default")
      (node (ref "C2") (pin "1") (pinfunction "1_1") (pintype "passive"))
      (node (ref "C3") (pin "2") (pinfunction "2_2") (pintype "passive"))
      (node (ref "PR1") (pin "10D") (pinfunction "P94_10D") (pintype "bidirectional"))
      (node (ref "PR1") (pin "1D") (pinfunction "P4_1D") (pintype "bidirectional"))
      (node (ref "PR1") (pin "2D") (pinfunction "P14_2D") (pintype "bidirectional"))
      (node (ref "PR1") (pin "3D") (pinfunction "P24_3D") (pintype "bidirectional"))
      (node (ref "PR1") (pin "4D") (pinfunction "P34_4D") (pintype "bidirectional"))
      (node (ref "PR1") (pin "5D") (pinfunction "P44_5D") (pintype "bidirectional"))
      (node (ref "PR1") (pin "6D") (pinfunction "P54_6D") (pintype "bidirectional"))
      (node (ref "PR1") (pin "7D") (pinfunction "P64_7D") (pintype "bidirectional"))
      (node (ref "PR1") (pin "8D") (pinfunction "P74_8D") (pintype "bidirectional"))
      (node (ref "PR1") (pin "9D") (pinfunction "P84_9D") (pintype "bidirectional"))
      (node (ref "Q1") (pin "2") (pinfunction "VOUT/C1_2") (pintype "output"))
      (node (ref "Q1") (pin "3") (pinfunction "VOUT/C1_3") (pintype "output"))
      (node (ref "RN1") (pin "8") (pinfunction "2_8") (pintype "passive"))
    )
    (net (code "78") (name "V2") (class "Default")
      (node (ref "C5") (pin "1") (pinfunction "1_1") (pintype "passive"))
      (node (ref "C6") (pin "2") (pinfunction "2_2") (pintype "passive"))
      (node (ref "PR1") (pin "10G") (pinfunction "P97_10G") (pintype "bidirectional"))
      (node (ref "PR1") (pin "1G") (pinfunction "P7_1G") (pintype "bidirectional"))
      (node (ref "PR1") (pin "2G") (pinfunction "P17_2G") (pintype "bidirectional"))
      (node (ref "PR1") (pin "3G") (pinfunction "P27_3G") (pintype "bidirectional"))
      (node (ref "PR1") (pin "4G") (pinfunction "P37_4G") (pintype "bidirectional"))
      (node (ref "PR1") (pin "5G") (pinfunction "P47_5G") (pintype "bidirectional"))
      (node (ref "PR1") (pin "6G") (pinfunction "P57_6G") (pintype "bidirectional"))
      (node (ref "PR1") (pin "7G") (pinfunction "P67_7G") (pintype "bidirectional"))
      (node (ref "PR1") (pin "8G") (pinfunction "P77_8G") (pintype "bidirectional"))
      (node (ref "PR1") (pin "9G") (pinfunction "P87_9G") (pintype "bidirectional"))
      (node (ref "Q2") (pin "2") (pinfunction "VOUT/C1_2") (pintype "output"))
      (node (ref "Q2") (pin "3") (pinfunction "VOUT/C1_3") (pintype "output"))
      (node (ref "RN1") (pin "6") (pinfunction "2_6") (pintype "passive"))
    )
    (net (code "79") (name "VIN") (class "Default")
      (node (ref "C10") (pin "1") (pinfunction "1_1") (pintype "passive"))
      (node (ref "C15") (pin "1") (pinfunction "1_1") (pintype "passive"))
      (node (ref "C7") (pin "2") (pinfunction "2_2") (pintype "passive"))
      (node (ref "F1") (pin "2") (pinfunction "2_2") (pintype "passive"))
      (node (ref "Q3") (pin "4") (pinfunction "VIN/R1_4") (pintype "input"))
      (node (ref "R7") (pin "2") (pinfunction "2_2") (pintype "passive"))
      (node (ref "SV3") (pin "17") (pinfunction "17_17") (pintype "passive"))
      (node (ref "U4") (pin "7") (pinfunction "VIN_7") (pintype "power_in"))
    )
    (net (code "80") (name "unconnected-(U4-NC_2-Pad2)") (class "Default")
      (node (ref "U4") (pin "2") (pinfunction "NC_2_2") (pintype "no_connect"))
    )
    (net (code "81") (name "unconnected-(U4-NC_3-Pad3)") (class "Default")
      (node (ref "U4") (pin "3") (pinfunction "NC_3_3") (pintype "no_connect"))
    )
  )
)
